# 06-ModuleControls.net
KiCad netlist of a schematic drawn in Altium Designer
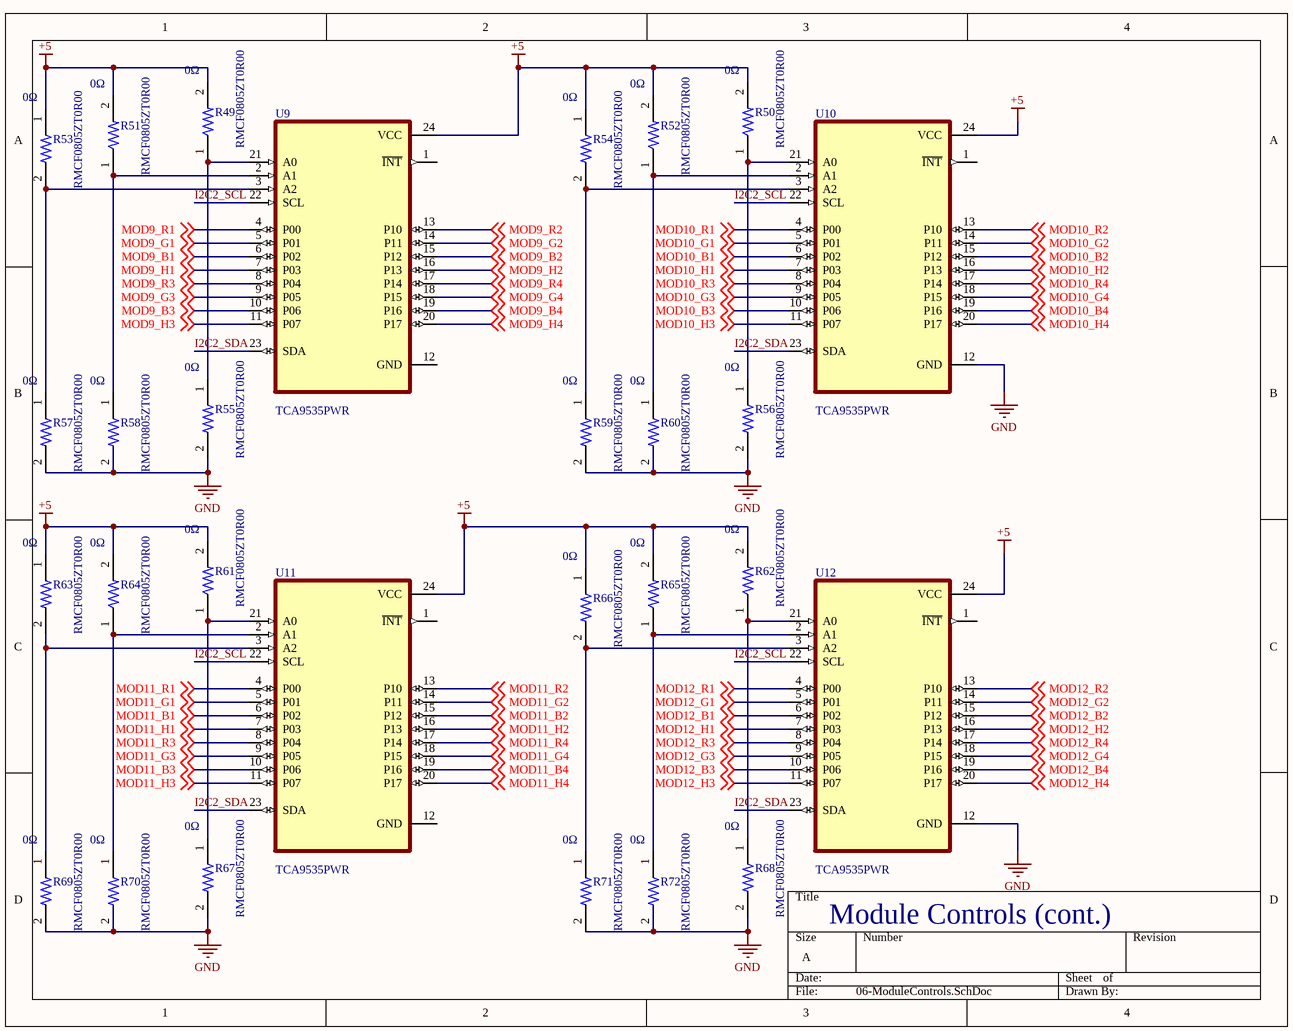
[diagram p0: 06-ModuleControls.SchDoc]

(export (version "E")
  (design (tool "Eeschema 10.0.6"))
  (components
    (comp (ref "R49")
      (value "RMCF0805ZT0R00")
      (footprint "RESC2012X60N")
      (description "0 Ohms Jumper 0.125W, 1/8W Chip Resistor 0805 (2012 Metric) Automotive AEC-Q200 Thick Film")
      (fields (field (name "MF") "Stackpole Electronics") (field (name "RESITANCE") "0Ω"))
      (libsource (lib "base-board") (part "RMCF0805ZT0R00"))
    )
    (comp (ref "R50")
      (value "RMCF0805ZT0R00")
      (footprint "RESC2012X60N")
      (description "0 Ohms Jumper 0.125W, 1/8W Chip Resistor 0805 (2012 Metric) Automotive AEC-Q200 Thick Film")
      (fields (field (name "MF") "Stackpole Electronics") (field (name "RESITANCE") "0Ω"))
      (libsource (lib "base-board") (part "RMCF0805ZT0R00"))
    )
    (comp (ref "R51")
      (value "RMCF0805ZT0R00")
      (footprint "RESC2012X60N")
      (description "0 Ohms Jumper 0.125W, 1/8W Chip Resistor 0805 (2012 Metric) Automotive AEC-Q200 Thick Film")
      (fields (field (name "MF") "Stackpole Electronics") (field (name "RESITANCE") "0Ω"))
      (libsource (lib "base-board") (part "RMCF0805ZT0R00"))
    )
    (comp (ref "R52")
      (value "RMCF0805ZT0R00")
      (footprint "RESC2012X60N")
      (description "0 Ohms Jumper 0.125W, 1/8W Chip Resistor 0805 (2012 Metric) Automotive AEC-Q200 Thick Film")
      (fields (field (name "MF") "Stackpole Electronics") (field (name "RESITANCE") "0Ω"))
      (libsource (lib "base-board") (part "RMCF0805ZT0R00"))
    )
    (comp (ref "R53")
      (value "RMCF0805ZT0R00")
      (footprint "RESC2012X60N")
      (description "0 Ohms Jumper 0.125W, 1/8W Chip Resistor 0805 (2012 Metric) Automotive AEC-Q200 Thick Film")
      (fields (field (name "MF") "Stackpole Electronics") (field (name "RESITANCE") "0Ω"))
      (libsource (lib "base-board") (part "RMCF0805ZT0R00"))
    )
    (comp (ref "R54")
      (value "RMCF0805ZT0R00")
      (footprint "RESC2012X60N")
      (description "0 Ohms Jumper 0.125W, 1/8W Chip Resistor 0805 (2012 Metric) Automotive AEC-Q200 Thick Film")
      (fields (field (name "MF") "Stackpole Electronics") (field (name "RESITANCE") "0Ω"))
      (libsource (lib "base-board") (part "RMCF0805ZT0R00"))
    )
    (comp (ref "R55")
      (value "RMCF0805ZT0R00")
      (footprint "RESC2012X60N")
      (description "0 Ohms Jumper 0.125W, 1/8W Chip Resistor 0805 (2012 Metric) Automotive AEC-Q200 Thick Film")
      (fields (field (name "MF") "Stackpole Electronics") (field (name "RESITANCE") "0Ω"))
      (libsource (lib "base-board") (part "RMCF0805ZT0R00"))
    )
    (comp (ref "R56")
      (value "RMCF0805ZT0R00")
      (footprint "RESC2012X60N")
      (description "0 Ohms Jumper 0.125W, 1/8W Chip Resistor 0805 (2012 Metric) Automotive AEC-Q200 Thick Film")
      (fields (field (name "MF") "Stackpole Electronics") (field (name "RESITANCE") "0Ω"))
      (libsource (lib "base-board") (part "RMCF0805ZT0R00"))
    )
    (comp (ref "R57")
      (value "RMCF0805ZT0R00")
      (footprint "RESC2012X60N")
      (description "0 Ohms Jumper 0.125W, 1/8W Chip Resistor 0805 (2012 Metric) Automotive AEC-Q200 Thick Film")
      (fields (field (name "MF") "Stackpole Electronics") (field (name "RESITANCE") "0Ω"))
      (libsource (lib "base-board") (part "RMCF0805ZT0R00"))
    )
    (comp (ref "R58")
      (value "RMCF0805ZT0R00")
      (footprint "RESC2012X60N")
      (description "0 Ohms Jumper 0.125W, 1/8W Chip Resistor 0805 (2012 Metric) Automotive AEC-Q200 Thick Film")
      (fields (field (name "MF") "Stackpole Electronics") (field (name "RESITANCE") "0Ω"))
      (libsource (lib "base-board") (part "RMCF0805ZT0R00"))
    )
    (comp (ref "R59")
      (value "RMCF0805ZT0R00")
      (footprint "RESC2012X60N")
      (description "0 Ohms Jumper 0.125W, 1/8W Chip Resistor 0805 (2012 Metric) Automotive AEC-Q200 Thick Film")
      (fields (field (name "MF") "Stackpole Electronics") (field (name "RESITANCE") "0Ω"))
      (libsource (lib "base-board") (part "RMCF0805ZT0R00"))
    )
    (comp (ref "R60")
      (value "RMCF0805ZT0R00")
      (footprint "RESC2012X60N")
      (description "0 Ohms Jumper 0.125W, 1/8W Chip Resistor 0805 (2012 Metric) Automotive AEC-Q200 Thick Film")
      (fields (field (name "MF") "Stackpole Electronics") (field (name "RESITANCE") "0Ω"))
      (libsource (lib "base-board") (part "RMCF0805ZT0R00"))
    )
    (comp (ref "R61")
      (value "RMCF0805ZT0R00")
      (footprint "RESC2012X60N")
      (description "0 Ohms Jumper 0.125W, 1/8W Chip Resistor 0805 (2012 Metric) Automotive AEC-Q200 Thick Film")
      (fields (field (name "MF") "Stackpole Electronics") (field (name "RESITANCE") "0Ω"))
      (libsource (lib "base-board") (part "RMCF0805ZT0R00"))
    )
    (comp (ref "R62")
      (value "RMCF0805ZT0R00")
      (footprint "RESC2012X60N")
      (description "0 Ohms Jumper 0.125W, 1/8W Chip Resistor 0805 (2012 Metric) Automotive AEC-Q200 Thick Film")
      (fields (field (name "MF") "Stackpole Electronics") (field (name "RESITANCE") "0Ω"))
      (libsource (lib "base-board") (part "RMCF0805ZT0R00"))
    )
    (comp (ref "R63")
      (value "RMCF0805ZT0R00")
      (footprint "RESC2012X60N")
      (description "0 Ohms Jumper 0.125W, 1/8W Chip Resistor 0805 (2012 Metric) Automotive AEC-Q200 Thick Film")
      (fields (field (name "MF") "Stackpole Electronics") (field (name "RESITANCE") "0Ω"))
      (libsource (lib "base-board") (part "RMCF0805ZT0R00"))
    )
    (comp (ref "R64")
      (value "RMCF0805ZT0R00")
      (footprint "RESC2012X60N")
      (description "0 Ohms Jumper 0.125W, 1/8W Chip Resistor 0805 (2012 Metric) Automotive AEC-Q200 Thick Film")
      (fields (field (name "MF") "Stackpole Electronics") (field (name "RESITANCE") "0Ω"))
      (libsource (lib "base-board") (part "RMCF0805ZT0R00"))
    )
    (comp (ref "R65")
      (value "RMCF0805ZT0R00")
      (footprint "RESC2012X60N")
      (description "0 Ohms Jumper 0.125W, 1/8W Chip Resistor 0805 (2012 Metric) Automotive AEC-Q200 Thick Film")
      (fields (field (name "MF") "Stackpole Electronics") (field (name "RESITANCE") "0Ω"))
      (libsource (lib "base-board") (part "RMCF0805ZT0R00"))
    )
    (comp (ref "R66")
      (value "RMCF0805ZT0R00")
      (footprint "RESC2012X60N")
      (description "0 Ohms Jumper 0.125W, 1/8W Chip Resistor 0805 (2012 Metric) Automotive AEC-Q200 Thick Film")
      (fields (field (name "MF") "Stackpole Electronics") (field (name "RESITANCE") "0Ω"))
      (libsource (lib "base-board") (part "RMCF0805ZT0R00"))
    )
    (comp (ref "R67")
      (value "RMCF0805ZT0R00")
      (footprint "RESC2012X60N")
      (description "0 Ohms Jumper 0.125W, 1/8W Chip Resistor 0805 (2012 Metric) Automotive AEC-Q200 Thick Film")
      (fields (field (name "MF") "Stackpole Electronics") (field (name "RESITANCE") "0Ω"))
      (libsource (lib "base-board") (part "RMCF0805ZT0R00"))
    )
    (comp (ref "R68")
      (value "RMCF0805ZT0R00")
      (footprint "RESC2012X60N")
      (description "0 Ohms Jumper 0.125W, 1/8W Chip Resistor 0805 (2012 Metric) Automotive AEC-Q200 Thick Film")
      (fields (field (name "MF") "Stackpole Electronics") (field (name "RESITANCE") "0Ω"))
      (libsource (lib "base-board") (part "RMCF0805ZT0R00"))
    )
    (comp (ref "R69")
      (value "RMCF0805ZT0R00")
      (footprint "RESC2012X60N")
      (description "0 Ohms Jumper 0.125W, 1/8W Chip Resistor 0805 (2012 Metric) Automotive AEC-Q200 Thick Film")
      (fields (field (name "MF") "Stackpole Electronics") (field (name "RESITANCE") "0Ω"))
      (libsource (lib "base-board") (part "RMCF0805ZT0R00"))
    )
    (comp (ref "R70")
      (value "RMCF0805ZT0R00")
      (footprint "RESC2012X60N")
      (description "0 Ohms Jumper 0.125W, 1/8W Chip Resistor 0805 (2012 Metric) Automotive AEC-Q200 Thick Film")
      (fields (field (name "MF") "Stackpole Electronics") (field (name "RESITANCE") "0Ω"))
      (libsource (lib "base-board") (part "RMCF0805ZT0R00"))
    )
    (comp (ref "R71")
      (value "RMCF0805ZT0R00")
      (footprint "RESC2012X60N")
      (description "0 Ohms Jumper 0.125W, 1/8W Chip Resistor 0805 (2012 Metric) Automotive AEC-Q200 Thick Film")
      (fields (field (name "MF") "Stackpole Electronics") (field (name "RESITANCE") "0Ω"))
      (libsource (lib "base-board") (part "RMCF0805ZT0R00"))
    )
    (comp (ref "R72")
      (value "RMCF0805ZT0R00")
      (footprint "RESC2012X60N")
      (description "0 Ohms Jumper 0.125W, 1/8W Chip Resistor 0805 (2012 Metric) Automotive AEC-Q200 Thick Film")
      (fields (field (name "MF") "Stackpole Electronics") (field (name "RESITANCE") "0Ω"))
      (libsource (lib "base-board") (part "RMCF0805ZT0R00"))
    )
    (comp (ref "U9")
      (value "TCA9535PWR")
      (footprint "SOP65P640X120-24N")
      (fields (field (name "MF") "Texas Instruments"))
      (libsource (lib "base-board") (part "TCA9535PWR"))
    )
    (comp (ref "U10")
      (value "TCA9535PWR")
      (footprint "SOP65P640X120-24N")
      (fields (field (name "MF") "Texas Instruments"))
      (libsource (lib "base-board") (part "TCA9535PWR"))
    )
    (comp (ref "U11")
      (value "TCA9535PWR")
      (footprint "SOP65P640X120-24N")
      (fields (field (name "MF") "Texas Instruments"))
      (libsource (lib "base-board") (part "TCA9535PWR"))
    )
    (comp (ref "U12")
      (value "TCA9535PWR")
      (footprint "SOP65P640X120-24N")
      (fields (field (name "MF") "Texas Instruments"))
      (libsource (lib "base-board") (part "TCA9535PWR"))
    )
  )
  (nets
    (net (code "1") (name "+5") (class "Default")
      (node (ref "R49") (pin "2") (pinfunction "2_2") (pintype "passive"))
      (node (ref "R50") (pin "2") (pinfunction "2_2") (pintype "passive"))
      (node (ref "R51") (pin "2") (pinfunction "2_2") (pintype "passive"))
      (node (ref "R52") (pin "2") (pinfunction "2_2") (pintype "passive"))
      (node (ref "R53") (pin "1") (pinfunction "1_1") (pintype "passive"))
      (node (ref "R54") (pin "1") (pinfunction "1_1") (pintype "passive"))
      (node (ref "R61") (pin "2") (pinfunction "2_2") (pintype "passive"))
      (node (ref "R62") (pin "2") (pinfunction "2_2") (pintype "passive"))
      (node (ref "R63") (pin "1") (pinfunction "1_1") (pintype "passive"))
      (node (ref "R64") (pin "2") (pinfunction "2_2") (pintype "passive"))
      (node (ref "R65") (pin "2") (pinfunction "2_2") (pintype "passive"))
      (node (ref "R66") (pin "1") (pinfunction "1_1") (pintype "passive"))
      (node (ref "U10") (pin "24") (pinfunction "VCC_24") (pintype "power_in"))
      (node (ref "U11") (pin "24") (pinfunction "VCC_24") (pintype "power_in"))
      (node (ref "U12") (pin "24") (pinfunction "VCC_24") (pintype "power_in"))
      (node (ref "U9") (pin "24") (pinfunction "VCC_24") (pintype "power_in"))
    )
    (net (code "2") (name "/I2C2_SCL") (class "Default")
      (node (ref "U10") (pin "22") (pinfunction "SCL_22") (pintype "input"))
      (node (ref "U11") (pin "22") (pinfunction "SCL_22") (pintype "input"))
      (node (ref "U12") (pin "22") (pinfunction "SCL_22") (pintype "input"))
      (node (ref "U9") (pin "22") (pinfunction "SCL_22") (pintype "input"))
    )
    (net (code "3") (name "/I2C2_SDA") (class "Default")
      (node (ref "U10") (pin "23") (pinfunction "SDA_23") (pintype "bidirectional"))
      (node (ref "U11") (pin "23") (pinfunction "SDA_23") (pintype "bidirectional"))
      (node (ref "U12") (pin "23") (pinfunction "SDA_23") (pintype "bidirectional"))
      (node (ref "U9") (pin "23") (pinfunction "SDA_23") (pintype "bidirectional"))
    )
    (net (code "4") (name "GND") (class "Default")
      (node (ref "R55") (pin "2") (pinfunction "2_2") (pintype "passive"))
      (node (ref "R56") (pin "2") (pinfunction "2_2") (pintype "passive"))
      (node (ref "R57") (pin "2") (pinfunction "2_2") (pintype "passive"))
      (node (ref "R58") (pin "2") (pinfunction "2_2") (pintype "passive"))
      (node (ref "R59") (pin "2") (pinfunction "2_2") (pintype "passive"))
      (node (ref "R60") (pin "2") (pinfunction "2_2") (pintype "passive"))
      (node (ref "R67") (pin "2") (pinfunction "2_2") (pintype "passive"))
      (node (ref "R68") (pin "2") (pinfunction "2_2") (pintype "passive"))
      (node (ref "R69") (pin "2") (pinfunction "2_2") (pintype "passive"))
      (node (ref "R70") (pin "2") (pinfunction "2_2") (pintype "passive"))
      (node (ref "R71") (pin "2") (pinfunction "2_2") (pintype "passive"))
      (node (ref "R72") (pin "2") (pinfunction "2_2") (pintype "passive"))
      (node (ref "U10") (pin "12") (pinfunction "GND_12") (pintype "power_in"))
      (node (ref "U12") (pin "12") (pinfunction "GND_12") (pintype "power_in"))
    )
    (net (code "5") (name "MOD9_B1") (class "Default")
      (node (ref "U9") (pin "6") (pinfunction "P02_6") (pintype "bidirectional"))
    )
    (net (code "6") (name "MOD9_B2") (class "Default")
      (node (ref "U9") (pin "15") (pinfunction "P12_15") (pintype "bidirectional"))
    )
    (net (code "7") (name "MOD9_B3") (class "Default")
      (node (ref "U9") (pin "10") (pinfunction "P06_10") (pintype "bidirectional"))
    )
    (net (code "8") (name "MOD9_B4") (class "Default")
      (node (ref "U9") (pin "19") (pinfunction "P16_19") (pintype "bidirectional"))
    )
    (net (code "9") (name "MOD9_G1") (class "Default")
      (node (ref "U9") (pin "5") (pinfunction "P01_5") (pintype "bidirectional"))
    )
    (net (code "10") (name "MOD9_G2") (class "Default")
      (node (ref "U9") (pin "14") (pinfunction "P11_14") (pintype "bidirectional"))
    )
    (net (code "11") (name "MOD9_G3") (class "Default")
      (node (ref "U9") (pin "9") (pinfunction "P05_9") (pintype "bidirectional"))
    )
    (net (code "12") (name "MOD9_G4") (class "Default")
      (node (ref "U9") (pin "18") (pinfunction "P15_18") (pintype "bidirectional"))
    )
    (net (code "13") (name "MOD9_H1") (class "Default")
      (node (ref "U9") (pin "7") (pinfunction "P03_7") (pintype "bidirectional"))
    )
    (net (code "14") (name "MOD9_H2") (class "Default")
      (node (ref "U9") (pin "16") (pinfunction "P13_16") (pintype "bidirectional"))
    )
    (net (code "15") (name "MOD9_H3") (class "Default")
      (node (ref "U9") (pin "11") (pinfunction "P07_11") (pintype "bidirectional"))
    )
    (net (code "16") (name "MOD9_H4") (class "Default")
      (node (ref "U9") (pin "20") (pinfunction "P17_20") (pintype "bidirectional"))
    )
    (net (code "17") (name "MOD9_R1") (class "Default")
      (node (ref "U9") (pin "4") (pinfunction "P00_4") (pintype "bidirectional"))
    )
    (net (code "18") (name "MOD9_R2") (class "Default")
      (node (ref "U9") (pin "13") (pinfunction "P10_13") (pintype "bidirectional"))
    )
    (net (code "19") (name "MOD9_R3") (class "Default")
      (node (ref "U9") (pin "8") (pinfunction "P04_8") (pintype "bidirectional"))
    )
    (net (code "20") (name "MOD9_R4") (class "Default")
      (node (ref "U9") (pin "17") (pinfunction "P14_17") (pintype "bidirectional"))
    )
    (net (code "21") (name "MOD10_B1") (class "Default")
      (node (ref "U10") (pin "6") (pinfunction "P02_6") (pintype "bidirectional"))
    )
    (net (code "22") (name "MOD10_B2") (class "Default")
      (node (ref "U10") (pin "15") (pinfunction "P12_15") (pintype "bidirectional"))
    )
    (net (code "23") (name "MOD10_B3") (class "Default")
      (node (ref "U10") (pin "10") (pinfunction "P06_10") (pintype "bidirectional"))
    )
    (net (code "24") (name "MOD10_B4") (class "Default")
      (node (ref "U10") (pin "19") (pinfunction "P16_19") (pintype "bidirectional"))
    )
    (net (code "25") (name "MOD10_G1") (class "Default")
      (node (ref "U10") (pin "5") (pinfunction "P01_5") (pintype "bidirectional"))
    )
    (net (code "26") (name "MOD10_G2") (class "Default")
      (node (ref "U10") (pin "14") (pinfunction "P11_14") (pintype "bidirectional"))
    )
    (net (code "27") (name "MOD10_G3") (class "Default")
      (node (ref "U10") (pin "9") (pinfunction "P05_9") (pintype "bidirectional"))
    )
    (net (code "28") (name "MOD10_G4") (class "Default")
      (node (ref "U10") (pin "18") (pinfunction "P15_18") (pintype "bidirectional"))
    )
    (net (code "29") (name "MOD10_H1") (class "Default")
      (node (ref "U10") (pin "7") (pinfunction "P03_7") (pintype "bidirectional"))
    )
    (net (code "30") (name "MOD10_H2") (class "Default")
      (node (ref "U10") (pin "16") (pinfunction "P13_16") (pintype "bidirectional"))
    )
    (net (code "31") (name "MOD10_H3") (class "Default")
      (node (ref "U10") (pin "11") (pinfunction "P07_11") (pintype "bidirectional"))
    )
    (net (code "32") (name "MOD10_H4") (class "Default")
      (node (ref "U10") (pin "20") (pinfunction "P17_20") (pintype "bidirectional"))
    )
    (net (code "33") (name "MOD10_R1") (class "Default")
      (node (ref "U10") (pin "4") (pinfunction "P00_4") (pintype "bidirectional"))
    )
    (net (code "34") (name "MOD10_R2") (class "Default")
      (node (ref "U10") (pin "13") (pinfunction "P10_13") (pintype "bidirectional"))
    )
    (net (code "35") (name "MOD10_R3") (class "Default")
      (node (ref "U10") (pin "8") (pinfunction "P04_8") (pintype "bidirectional"))
    )
    (net (code "36") (name "MOD10_R4") (class "Default")
      (node (ref "U10") (pin "17") (pinfunction "P14_17") (pintype "bidirectional"))
    )
    (net (code "37") (name "MOD11_B1") (class "Default")
      (node (ref "U11") (pin "6") (pinfunction "P02_6") (pintype "bidirectional"))
    )
    (net (code "38") (name "MOD11_B2") (class "Default")
      (node (ref "U11") (pin "15") (pinfunction "P12_15") (pintype "bidirectional"))
    )
    (net (code "39") (name "MOD11_B3") (class "Default")
      (node (ref "U11") (pin "10") (pinfunction "P06_10") (pintype "bidirectional"))
    )
    (net (code "40") (name "MOD11_B4") (class "Default")
      (node (ref "U11") (pin "19") (pinfunction "P16_19") (pintype "bidirectional"))
    )
    (net (code "41") (name "MOD11_G1") (class "Default")
      (node (ref "U11") (pin "5") (pinfunction "P01_5") (pintype "bidirectional"))
    )
    (net (code "42") (name "MOD11_G2") (class "Default")
      (node (ref "U11") (pin "14") (pinfunction "P11_14") (pintype "bidirectional"))
    )
    (net (code "43") (name "MOD11_G3") (class "Default")
      (node (ref "U11") (pin "9") (pinfunction "P05_9") (pintype "bidirectional"))
    )
    (net (code "44") (name "MOD11_G4") (class "Default")
      (node (ref "U11") (pin "18") (pinfunction "P15_18") (pintype "bidirectional"))
    )
    (net (code "45") (name "MOD11_H1") (class "Default")
      (node (ref "U11") (pin "7") (pinfunction "P03_7") (pintype "bidirectional"))
    )
    (net (code "46") (name "MOD11_H2") (class "Default")
      (node (ref "U11") (pin "16") (pinfunction "P13_16") (pintype "bidirectional"))
    )
    (net (code "47") (name "MOD11_H3") (class "Default")
      (node (ref "U11") (pin "11") (pinfunction "P07_11") (pintype "bidirectional"))
    )
    (net (code "48") (name "MOD11_H4") (class "Default")
      (node (ref "U11") (pin "20") (pinfunction "P17_20") (pintype "bidirectional"))
    )
    (net (code "49") (name "MOD11_R1") (class "Default")
      (node (ref "U11") (pin "4") (pinfunction "P00_4") (pintype "bidirectional"))
    )
    (net (code "50") (name "MOD11_R2") (class "Default")
      (node (ref "U11") (pin "13") (pinfunction "P10_13") (pintype "bidirectional"))
    )
    (net (code "51") (name "MOD11_R3") (class "Default")
      (node (ref "U11") (pin "8") (pinfunction "P04_8") (pintype "bidirectional"))
    )
    (net (code "52") (name "MOD11_R4") (class "Default")
      (node (ref "U11") (pin "17") (pinfunction "P14_17") (pintype "bidirectional"))
    )
    (net (code "53") (name "MOD12_B1") (class "Default")
      (node (ref "U12") (pin "6") (pinfunction "P02_6") (pintype "bidirectional"))
    )
    (net (code "54") (name "MOD12_B2") (class "Default")
      (node (ref "U12") (pin "15") (pinfunction "P12_15") (pintype "bidirectional"))
    )
    (net (code "55") (name "MOD12_B3") (class "Default")
      (node (ref "U12") (pin "10") (pinfunction "P06_10") (pintype "bidirectional"))
    )
    (net (code "56") (name "MOD12_B4") (class "Default")
      (node (ref "U12") (pin "19") (pinfunction "P16_19") (pintype "bidirectional"))
    )
    (net (code "57") (name "MOD12_G1") (class "Default")
      (node (ref "U12") (pin "5") (pinfunction "P01_5") (pintype "bidirectional"))
    )
    (net (code "58") (name "MOD12_G2") (class "Default")
      (node (ref "U12") (pin "14") (pinfunction "P11_14") (pintype "bidirectional"))
    )
    (net (code "59") (name "MOD12_G3") (class "Default")
      (node (ref "U12") (pin "9") (pinfunction "P05_9") (pintype "bidirectional"))
    )
    (net (code "60") (name "MOD12_G4") (class "Default")
      (node (ref "U12") (pin "18") (pinfunction "P15_18") (pintype "bidirectional"))
    )
    (net (code "61") (name "MOD12_H1") (class "Default")
      (node (ref "U12") (pin "7") (pinfunction "P03_7") (pintype "bidirectional"))
    )
    (net (code "62") (name "MOD12_H2") (class "Default")
      (node (ref "U12") (pin "16") (pinfunction "P13_16") (pintype "bidirectional"))
    )
    (net (code "63") (name "MOD12_H3") (class "Default")
      (node (ref "U12") (pin "11") (pinfunction "P07_11") (pintype "bidirectional"))
    )
    (net (code "64") (name "MOD12_H4") (class "Default")
      (node (ref "U12") (pin "20") (pinfunction "P17_20") (pintype "bidirectional"))
    )
    (net (code "65") (name "MOD12_R1") (class "Default")
      (node (ref "U12") (pin "4") (pinfunction "P00_4") (pintype "bidirectional"))
    )
    (net (code "66") (name "MOD12_R2") (class "Default")
      (node (ref "U12") (pin "13") (pinfunction "P10_13") (pintype "bidirectional"))
    )
    (net (code "67") (name "MOD12_R3") (class "Default")
      (node (ref "U12") (pin "8") (pinfunction "P04_8") (pintype "bidirectional"))
    )
    (net (code "68") (name "MOD12_R4") (class "Default")
      (node (ref "U12") (pin "17") (pinfunction "P14_17") (pintype "bidirectional"))
    )
    (net (code "69") (name "Net-(U9-A0)") (class "Default")
      (node (ref "R49") (pin "1") (pinfunction "1_1") (pintype "passive"))
      (node (ref "R55") (pin "1") (pinfunction "1_1") (pintype "passive"))
      (node (ref "U9") (pin "21") (pinfunction "A0_21") (pintype "input"))
    )
    (net (code "70") (name "Net-(U9-A1)") (class "Default")
      (node (ref "R51") (pin "1") (pinfunction "1_1") (pintype "passive"))
      (node (ref "R58") (pin "1") (pinfunction "1_1") (pintype "passive"))
      (node (ref "U9") (pin "2") (pinfunction "A1_2") (pintype "input"))
    )
    (net (code "71") (name "Net-(U9-A2)") (class "Default")
      (node (ref "R53") (pin "2") (pinfunction "2_2") (pintype "passive"))
      (node (ref "R57") (pin "1") (pinfunction "1_1") (pintype "passive"))
      (node (ref "U9") (pin "3") (pinfunction "A2_3") (pintype "input"))
    )
    (net (code "72") (name "Net-(U10-A0)") (class "Default")
      (node (ref "R50") (pin "1") (pinfunction "1_1") (pintype "passive"))
      (node (ref "R56") (pin "1") (pinfunction "1_1") (pintype "passive"))
      (node (ref "U10") (pin "21") (pinfunction "A0_21") (pintype "input"))
    )
    (net (code "73") (name "Net-(U10-A1)") (class "Default")
      (node (ref "R52") (pin "1") (pinfunction "1_1") (pintype "passive"))
      (node (ref "R60") (pin "1") (pinfunction "1_1") (pintype "passive"))
      (node (ref "U10") (pin "2") (pinfunction "A1_2") (pintype "input"))
    )
    (net (code "74") (name "Net-(U10-A2)") (class "Default")
      (node (ref "R54") (pin "2") (pinfunction "2_2") (pintype "passive"))
      (node (ref "R59") (pin "1") (pinfunction "1_1") (pintype "passive"))
      (node (ref "U10") (pin "3") (pinfunction "A2_3") (pintype "input"))
    )
    (net (code "75") (name "Net-(U11-A0)") (class "Default")
      (node (ref "R61") (pin "1") (pinfunction "1_1") (pintype "passive"))
      (node (ref "R67") (pin "1") (pinfunction "1_1") (pintype "passive"))
      (node (ref "U11") (pin "21") (pinfunction "A0_21") (pintype "input"))
    )
    (net (code "76") (name "Net-(U11-A1)") (class "Default")
      (node (ref "R64") (pin "1") (pinfunction "1_1") (pintype "passive"))
      (node (ref "R70") (pin "1") (pinfunction "1_1") (pintype "passive"))
      (node (ref "U11") (pin "2") (pinfunction "A1_2") (pintype "input"))
    )
    (net (code "77") (name "Net-(U11-A2)") (class "Default")
      (node (ref "R63") (pin "2") (pinfunction "2_2") (pintype "passive"))
      (node (ref "R69") (pin "1") (pinfunction "1_1") (pintype "passive"))
      (node (ref "U11") (pin "3") (pinfunction "A2_3") (pintype "input"))
    )
    (net (code "78") (name "Net-(U12-A0)") (class "Default")
      (node (ref "R62") (pin "1") (pinfunction "1_1") (pintype "passive"))
      (node (ref "R68") (pin "1") (pinfunction "1_1") (pintype "passive"))
      (node (ref "U12") (pin "21") (pinfunction "A0_21") (pintype "input"))
    )
    (net (code "79") (name "Net-(U12-A1)") (class "Default")
      (node (ref "R65") (pin "1") (pinfunction "1_1") (pintype "passive"))
      (node (ref "R72") (pin "1") (pinfunction "1_1") (pintype "passive"))
      (node (ref "U12") (pin "2") (pinfunction "A1_2") (pintype "input"))
    )
    (net (code "80") (name "Net-(U12-A2)") (class "Default")
      (node (ref "R66") (pin "2") (pinfunction "2_2") (pintype "passive"))
      (node (ref "R71") (pin "1") (pinfunction "1_1") (pintype "passive"))
      (node (ref "U12") (pin "3") (pinfunction "A2_3") (pintype "input"))
    )
    (net (code "81") (name "unconnected-(U9-GND-Pad12)") (class "Default")
      (node (ref "U9") (pin "12") (pinfunction "GND_12") (pintype "power_in"))
    )
    (net (code "82") (name "unconnected-(U9-~{INT}-Pad1)") (class "Default")
      (node (ref "U9") (pin "1") (pinfunction "~{INT}_1") (pintype "output"))
    )
    (net (code "83") (name "unconnected-(U10-~{INT}-Pad1)") (class "Default")
      (node (ref "U10") (pin "1") (pinfunction "~{INT}_1") (pintype "output"))
    )
    (net (code "84") (name "unconnected-(U11-GND-Pad12)") (class "Default")
      (node (ref "U11") (pin "12") (pinfunction "GND_12") (pintype "power_in"))
    )
    (net (code "85") (name "unconnected-(U11-~{INT}-Pad1)") (class "Default")
      (node (ref "U11") (pin "1") (pinfunction "~{INT}_1") (pintype "output"))
    )
    (net (code "86") (name "unconnected-(U12-~{INT}-Pad1)") (class "Default")
      (node (ref "U12") (pin "1") (pinfunction "~{INT}_1") (pintype "output"))
    )
  )
)
